# MotorDriverConnector.net
KiCad netlist of a schematic drawn in Altium Designer
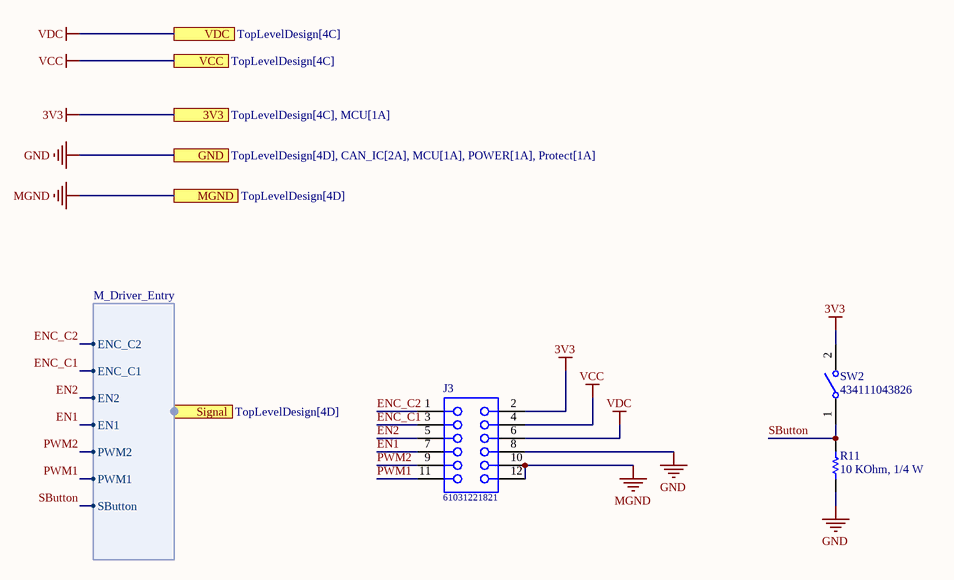
[diagram p0: MotorDriverConnector.SchDoc]

(export (version "E")
  (design (tool "Eeschema 10.0.6"))
  (components
    (comp (ref "J3")
      (value "61031221821")
      (footprint "61031221821")
      (description "WR-PHD Socket Header, SMT, pitch 2.54mm, Dual Row, Vertical, 12p")
      (fields (field (name "MANUFACTURER") "Wurth Elektronik"))
      (libsource (lib "Tin Tran") (part "613012243121"))
    )
    (comp (ref "R11")
      (value "10 KOhm, 1/4 W")
      (footprint "resistor_0603")
      (description "RES, size 0603, 10 KOhm, 1/4 W")
      (fields (field (name "Comment") "0006031031"))
      (libsource (lib "Tin Tran") (part "00060371541"))
    )
    (comp (ref "SW2")
      (value "434111043826")
      (footprint "WS-TASV_L6W3.5H4.3_4341x10438x6")
      (description "WS-TASV SMT Tact Switch, L6 x W3.5 x H4.3mm, 260g, SPST-NO, 12V, 50mA")
      (fields (field (name "MANUFACTURER") "Wurth Elektronik"))
      (libsource (lib "Tin Tran") (part "434111050826"))
    )
  )
  (nets
    (net (code "2") (name "/EN1") (class "Default")
      (node (ref "J3") (pin "7") (pinfunction "7_7") (pintype "passive"))
    )
    (net (code "3") (name "/EN2") (class "Default")
      (node (ref "J3") (pin "5") (pinfunction "5_5") (pintype "passive"))
    )
    (net (code "4") (name "/ENC_C1") (class "Default")
      (node (ref "J3") (pin "3") (pinfunction "3_3") (pintype "passive"))
    )
    (net (code "5") (name "/ENC_C2") (class "Default")
      (node (ref "J3") (pin "1") (pinfunction "1_1") (pintype "passive"))
    )
    (net (code "6") (name "/PWM1") (class "Default")
      (node (ref "J3") (pin "11") (pinfunction "11_11") (pintype "passive"))
    )
    (net (code "7") (name "/PWM2") (class "Default")
      (node (ref "J3") (pin "9") (pinfunction "9_9") (pintype "passive"))
    )
    (net (code "8") (name "/SButton") (class "Default")
      (node (ref "R11") (pin "2") (pinfunction "2_2") (pintype "passive"))
      (node (ref "SW2") (pin "1") (pinfunction "1_1") (pintype "passive"))
    )
    (net (code "10") (name "3V3") (class "Default")
      (node (ref "J3") (pin "2") (pinfunction "2_2") (pintype "passive"))
      (node (ref "SW2") (pin "2") (pinfunction "2_2") (pintype "passive"))
    )
    (net (code "11") (name "GND") (class "Default")
      (node (ref "J3") (pin "8") (pinfunction "8_8") (pintype "passive"))
      (node (ref "R11") (pin "1") (pinfunction "1_1") (pintype "passive"))
    )
    (net (code "12") (name "MGND") (class "Default")
      (node (ref "J3") (pin "10") (pinfunction "10_10") (pintype "passive"))
      (node (ref "J3") (pin "12") (pinfunction "12_12") (pintype "passive"))
    )
    (net (code "13") (name "VCC") (class "Default")
      (node (ref "J3") (pin "4") (pinfunction "4_4") (pintype "passive"))
    )
    (net (code "14") (name "VDC") (class "Default")
      (node (ref "J3") (pin "6") (pinfunction "6_6") (pintype "passive"))
    )
  )
)
